# vco1_components.net
KiCad netlist of a schematic drawn in EAGLE
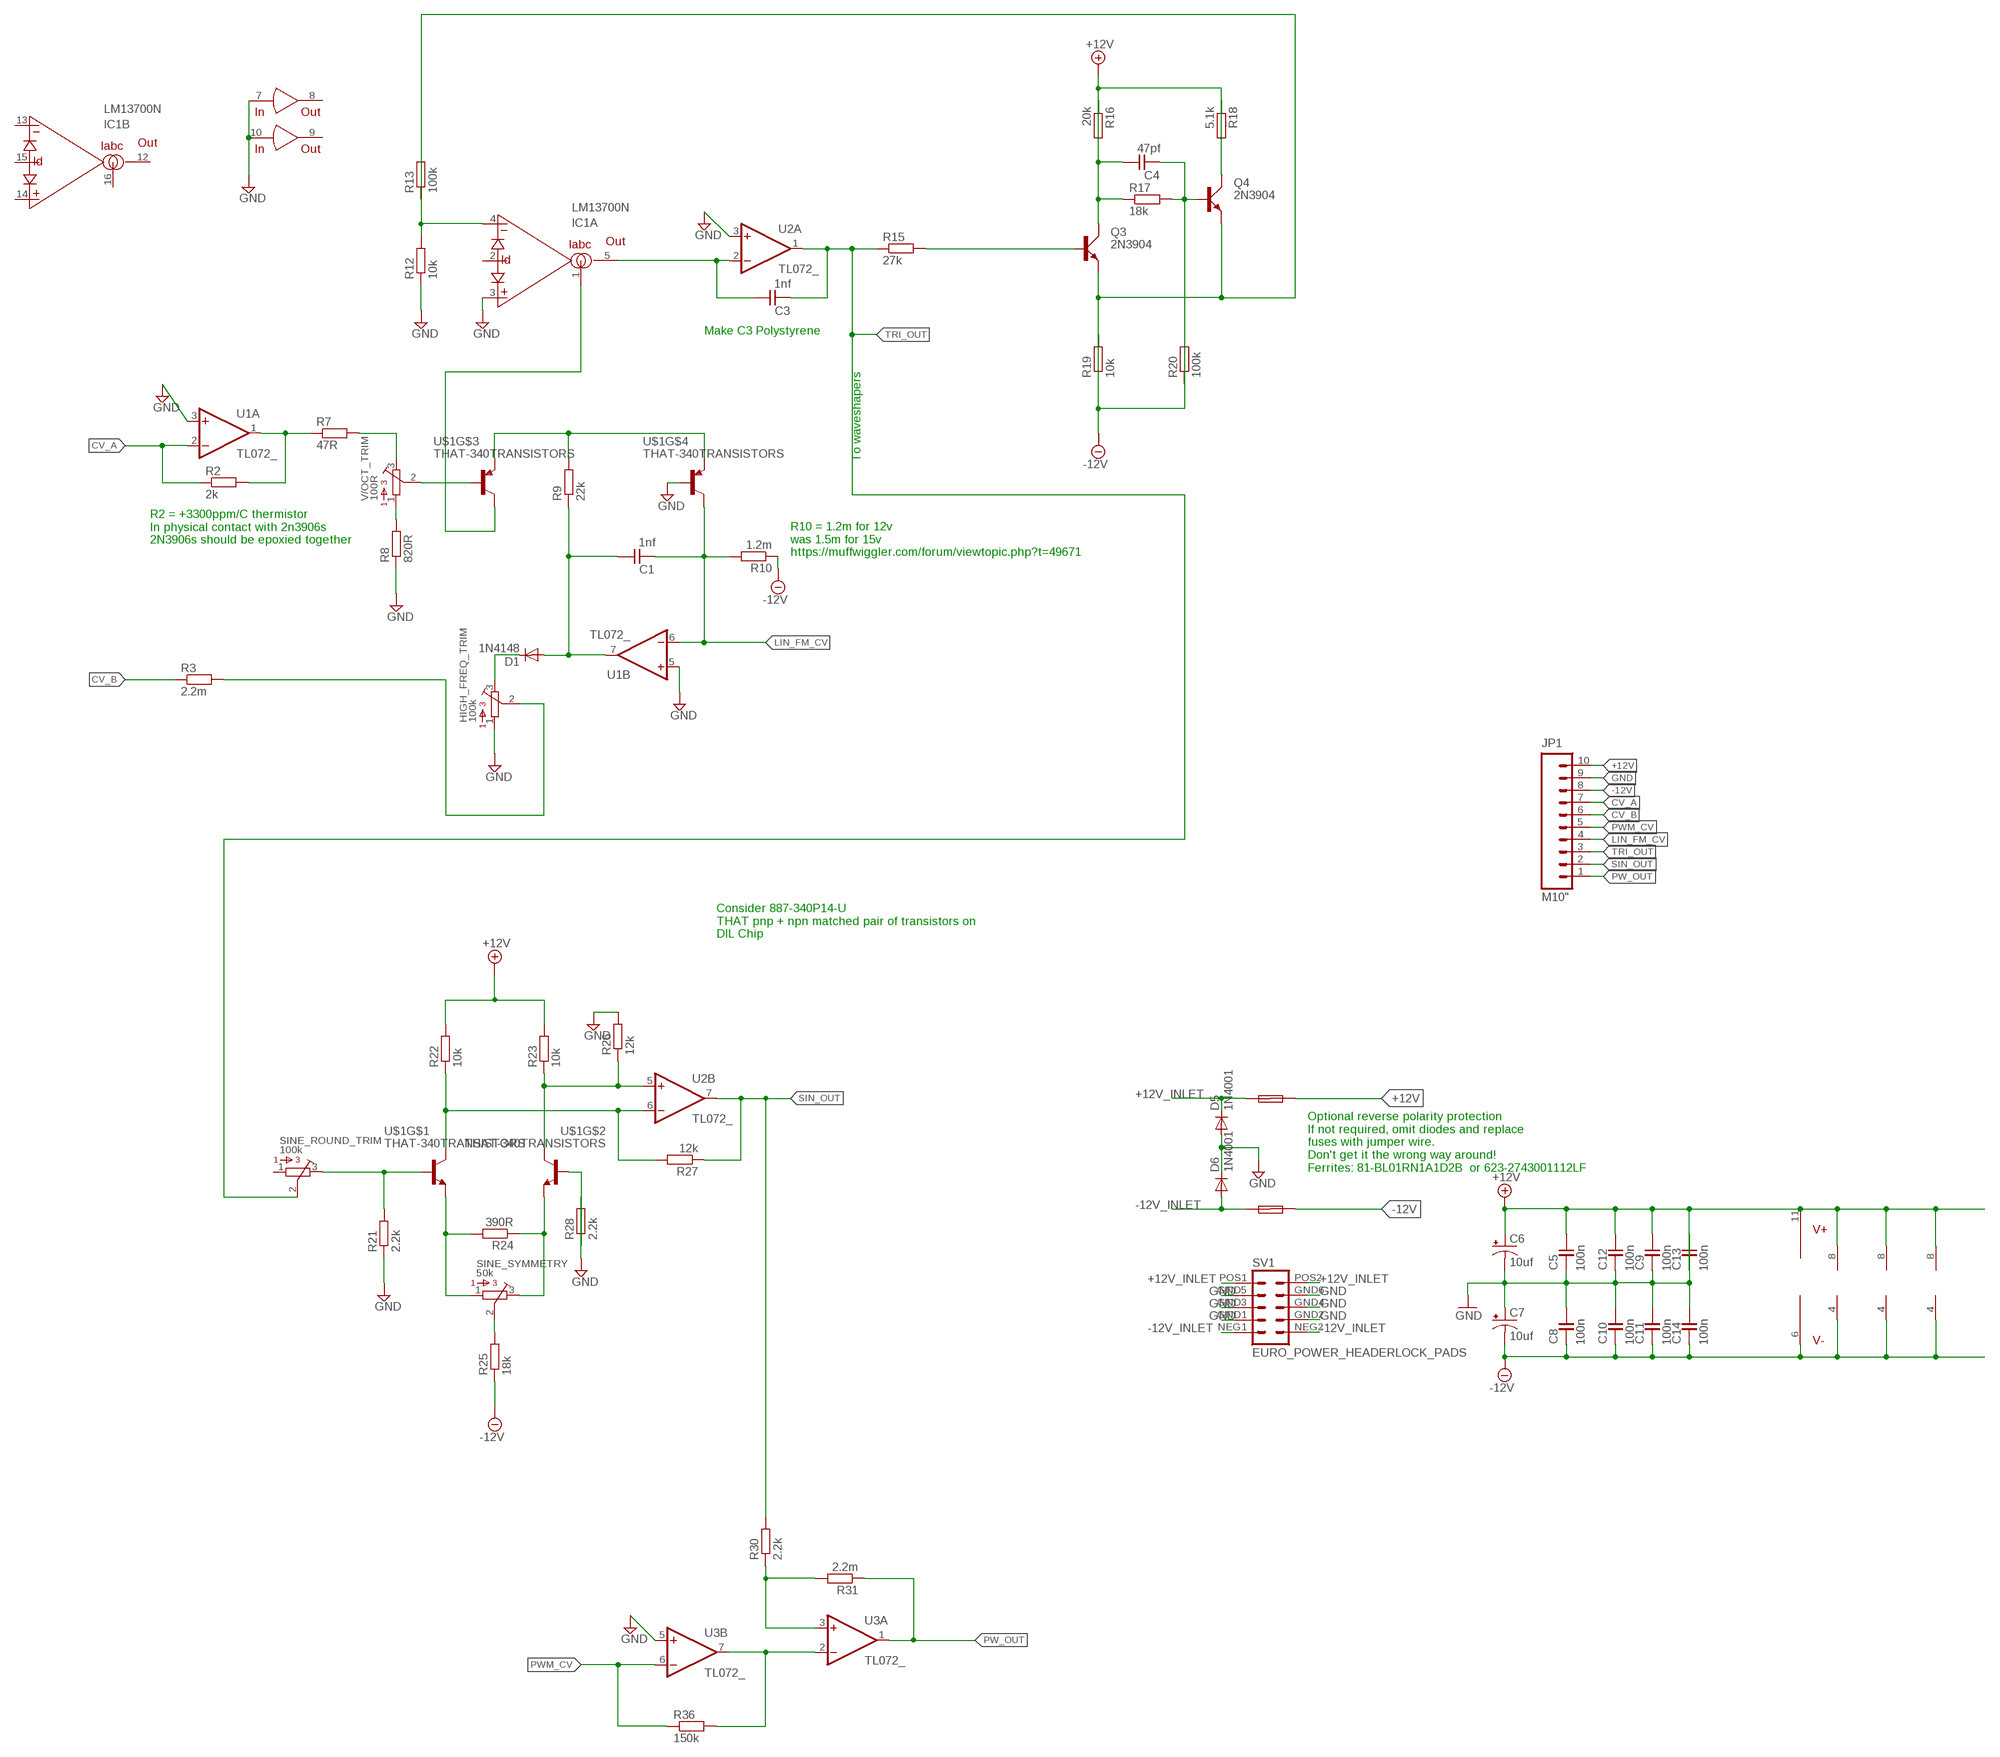
[diagram p0: schematic, sheet 1]

(export (version "E")
  (design (tool "Eeschema 10.0.6"))
  (components
    (comp (ref "C1")
      (value "1nf")
      (footprint "eagle-import:C050-024X044")
      (libsource (lib "eagle-import") (part "C-EU050-024X044"))
    )
    (comp (ref "C3")
      (value "1nf")
      (footprint "eagle-import:C050-024X044")
      (libsource (lib "eagle-import") (part "C-EU050-024X044"))
    )
    (comp (ref "C4")
      (value "47pf")
      (footprint "eagle-import:C050-024X044")
      (libsource (lib "eagle-import") (part "C-EU050-024X044"))
    )
    (comp (ref "C5")
      (value "100n")
      (footprint "eagle-import:C050-024X044")
      (libsource (lib "eagle-import") (part "C-EU050-024X044"))
    )
    (comp (ref "C6")
      (value "10uf")
      (footprint "eagle-import:CPOL-RADIAL-10UF-25V")
      (libsource (lib "eagle-import") (part "CAP_POLPTH2"))
    )
    (comp (ref "C7")
      (value "10uf")
      (footprint "eagle-import:CPOL-RADIAL-10UF-25V")
      (libsource (lib "eagle-import") (part "CAP_POLPTH2"))
    )
    (comp (ref "C8")
      (value "100n")
      (footprint "eagle-import:C050-024X044")
      (libsource (lib "eagle-import") (part "C-EU050-024X044"))
    )
    (comp (ref "C9")
      (value "100n")
      (footprint "eagle-import:C050-024X044")
      (libsource (lib "eagle-import") (part "C-EU050-024X044"))
    )
    (comp (ref "C10")
      (value "100n")
      (footprint "eagle-import:C050-024X044")
      (libsource (lib "eagle-import") (part "C-EU050-024X044"))
    )
    (comp (ref "C11")
      (value "100n")
      (footprint "eagle-import:C050-024X044")
      (libsource (lib "eagle-import") (part "C-EU050-024X044"))
    )
    (comp (ref "C12")
      (value "100n")
      (footprint "eagle-import:C050-024X044")
      (libsource (lib "eagle-import") (part "C-EU050-024X044"))
    )
    (comp (ref "C13")
      (value "100n")
      (footprint "eagle-import:C050-024X044")
      (libsource (lib "eagle-import") (part "C-EU050-024X044"))
    )
    (comp (ref "C14")
      (value "100n")
      (footprint "eagle-import:C050-024X044")
      (libsource (lib "eagle-import") (part "C-EU050-024X044"))
    )
    (comp (ref "D1")
      (value "1N4148")
      (footprint "eagle-import:DO35-7")
      (libsource (lib "eagle-import") (part "SMALL_DIODEDO35-7"))
    )
    (comp (ref "D5")
      (value "1N4001")
      (footprint "eagle-import:DO41-10")
      (libsource (lib "eagle-import") (part "1N4004"))
    )
    (comp (ref "D6")
      (value "1N4001")
      (footprint "eagle-import:DO41-10")
      (libsource (lib "eagle-import") (part "1N4004"))
    )
    (comp (ref "F1")
      (value "FUSE")
      (footprint "eagle-import:C050H075X075")
      (libsource (lib "eagle-import") (part "PTC_FUSEPOLY_FUSE"))
    )
    (comp (ref "F2")
      (value "FUSE")
      (footprint "eagle-import:C050H075X075")
      (libsource (lib "eagle-import") (part "PTC_FUSEPOLY_FUSE"))
    )
    (comp (ref "HIGH_FREQ_TRIM")
      (value "100k")
      (footprint "eagle-import:BOURNS_3362P_TRIMMER")
      (libsource (lib "eagle-import") (part "BOURNS_3362P_TRIMMERP"))
    )
    (comp (ref "IC1")
      (value "LM13700N")
      (footprint "eagle-import:DIL16")
      (libsource (lib "eagle-import") (part "LM13700N"))
    )
    (comp (ref "JP1")
      (value "M10\"")
      (footprint "eagle-import:1X10")
      (libsource (lib "eagle-import") (part "M10{dblquote}"))
    )
    (comp (ref "Q3")
      (value "2N3904")
      (footprint "eagle-import:TO92D")
      (libsource (lib "eagle-import") (part "2N3904"))
    )
    (comp (ref "Q4")
      (value "2N3904")
      (footprint "eagle-import:TO92D")
      (libsource (lib "eagle-import") (part "2N3904"))
    )
    (comp (ref "R2")
      (value "2k")
      (footprint "eagle-import:7MM_RESISTOR")
      (libsource (lib "eagle-import") (part "RESISTOR7MM"))
    )
    (comp (ref "R3")
      (value "2.2m")
      (footprint "eagle-import:7MM_RESISTOR")
      (libsource (lib "eagle-import") (part "RESISTOR7MM"))
    )
    (comp (ref "R7")
      (value "47R")
      (footprint "eagle-import:7MM_RESISTOR")
      (libsource (lib "eagle-import") (part "RESISTOR7MM"))
    )
    (comp (ref "R8")
      (value "820R")
      (footprint "eagle-import:7MM_RESISTOR")
      (libsource (lib "eagle-import") (part "RESISTOR7MM"))
    )
    (comp (ref "R9")
      (value "22k")
      (footprint "eagle-import:7MM_RESISTOR")
      (libsource (lib "eagle-import") (part "RESISTOR7MM"))
    )
    (comp (ref "R10")
      (value "1.2m")
      (footprint "eagle-import:7MM_RESISTOR")
      (libsource (lib "eagle-import") (part "RESISTOR7MM"))
    )
    (comp (ref "R12")
      (value "10k")
      (footprint "eagle-import:7MM_RESISTOR")
      (libsource (lib "eagle-import") (part "RESISTOR7MM"))
    )
    (comp (ref "R13")
      (value "100k")
      (footprint "eagle-import:7MM_RESISTOR")
      (libsource (lib "eagle-import") (part "RESISTOR7MM"))
    )
    (comp (ref "R15")
      (value "27k")
      (footprint "eagle-import:7MM_RESISTOR")
      (libsource (lib "eagle-import") (part "RESISTOR7MM"))
    )
    (comp (ref "R16")
      (value "20k")
      (footprint "eagle-import:7MM_RESISTOR")
      (libsource (lib "eagle-import") (part "RESISTOR7MM"))
    )
    (comp (ref "R17")
      (value "18k")
      (footprint "eagle-import:7MM_RESISTOR")
      (libsource (lib "eagle-import") (part "RESISTOR7MM"))
    )
    (comp (ref "R18")
      (value "5.1k")
      (footprint "eagle-import:7MM_RESISTOR")
      (libsource (lib "eagle-import") (part "RESISTOR7MM"))
    )
    (comp (ref "R19")
      (value "10k")
      (footprint "eagle-import:7MM_RESISTOR")
      (libsource (lib "eagle-import") (part "RESISTOR7MM"))
    )
    (comp (ref "R20")
      (value "100k")
      (footprint "eagle-import:7MM_RESISTOR")
      (libsource (lib "eagle-import") (part "RESISTOR7MM"))
    )
    (comp (ref "R21")
      (value "2.2k")
      (footprint "eagle-import:7MM_RESISTOR")
      (libsource (lib "eagle-import") (part "RESISTOR7MM"))
    )
    (comp (ref "R22")
      (value "10k")
      (footprint "eagle-import:7MM_RESISTOR")
      (libsource (lib "eagle-import") (part "RESISTOR7MM"))
    )
    (comp (ref "R23")
      (value "10k")
      (footprint "eagle-import:7MM_RESISTOR")
      (libsource (lib "eagle-import") (part "RESISTOR7MM"))
    )
    (comp (ref "R24")
      (value "390R")
      (footprint "eagle-import:7MM_RESISTOR")
      (libsource (lib "eagle-import") (part "RESISTOR7MM"))
    )
    (comp (ref "R25")
      (value "18k")
      (footprint "eagle-import:7MM_RESISTOR")
      (libsource (lib "eagle-import") (part "RESISTOR7MM"))
    )
    (comp (ref "R26")
      (value "12k")
      (footprint "eagle-import:7MM_RESISTOR")
      (libsource (lib "eagle-import") (part "RESISTOR7MM"))
    )
    (comp (ref "R27")
      (value "12k")
      (footprint "eagle-import:7MM_RESISTOR")
      (libsource (lib "eagle-import") (part "RESISTOR7MM"))
    )
    (comp (ref "R28")
      (value "2.2k")
      (footprint "eagle-import:7MM_RESISTOR")
      (libsource (lib "eagle-import") (part "RESISTOR7MM"))
    )
    (comp (ref "R30")
      (value "2.2k")
      (footprint "eagle-import:7MM_RESISTOR")
      (libsource (lib "eagle-import") (part "RESISTOR7MM"))
    )
    (comp (ref "R31")
      (value "2.2m")
      (footprint "eagle-import:7MM_RESISTOR")
      (libsource (lib "eagle-import") (part "RESISTOR7MM"))
    )
    (comp (ref "R36")
      (value "150k")
      (footprint "eagle-import:7MM_RESISTOR")
      (libsource (lib "eagle-import") (part "RESISTOR7MM"))
    )
    (comp (ref "SINE_ROUND_TRIM")
      (value "100k")
      (footprint "eagle-import:BOURNS_3362P_TRIMMER")
      (libsource (lib "eagle-import") (part "BOURNS_3362P_TRIMMERP"))
    )
    (comp (ref "SINE_SYMMETRY")
      (value "50k")
      (footprint "eagle-import:BOURNS_3362P_TRIMMER")
      (libsource (lib "eagle-import") (part "BOURNS_3362P_TRIMMERP"))
    )
    (comp (ref "SV1")
      (value "EURO_POWER_HEADERLOCK_PADS")
      (footprint "eagle-import:EURO_PWR_HEADER_LOCK")
      (libsource (lib "eagle-import") (part "EURO_POWER_HEADERLOCK_PADS"))
    )
    (comp (ref "U$1")
      (value "THAT-340TRANSISTORS")
      (footprint "eagle-import:THAT340")
      (libsource (lib "eagle-import") (part "THAT-340TRANSISTORS"))
    )
    (comp (ref "U1")
      (value "TL072_")
      (footprint "eagle-import:DIL08")
      (libsource (lib "eagle-import") (part "TL072_"))
    )
    (comp (ref "U2")
      (value "TL072_")
      (footprint "eagle-import:DIL08")
      (libsource (lib "eagle-import") (part "TL072_"))
    )
    (comp (ref "U3")
      (value "TL072_")
      (footprint "eagle-import:DIL08")
      (libsource (lib "eagle-import") (part "TL072_"))
    )
    (comp (ref "V/OCT_TRIM")
      (value "100R")
      (footprint "eagle-import:BOURNS_3362P_TRIMMER")
      (libsource (lib "eagle-import") (part "BOURNS_3362P_TRIMMERP"))
    )
  )
  (nets
    (net (code "1") (name "+12V") (class "Default")
      (node (ref "C12") (pin "1") (pinfunction "1_1") (pintype "passive"))
      (node (ref "C13") (pin "2") (pinfunction "2_2") (pintype "passive"))
      (node (ref "C5") (pin "1") (pinfunction "1_1") (pintype "passive"))
      (node (ref "C6") (pin "1") (pinfunction "+_1") (pintype "passive"))
      (node (ref "C9") (pin "1") (pinfunction "1_1") (pintype "passive"))
      (node (ref "F1") (pin "2") (pinfunction "P$2_2") (pintype "bidirectional"))
      (node (ref "IC1") (pin "11") (pinfunction "V+_11") (pintype "bidirectional"))
      (node (ref "JP1") (pin "10") (pinfunction "10_10") (pintype "passive"))
      (node (ref "R16") (pin "2") (pinfunction "2_2") (pintype "passive"))
      (node (ref "R18") (pin "2") (pinfunction "2_2") (pintype "passive"))
      (node (ref "R22") (pin "2") (pinfunction "2_2") (pintype "passive"))
      (node (ref "R23") (pin "2") (pinfunction "2_2") (pintype "passive"))
      (node (ref "U1") (pin "8") (pinfunction "V+_8") (pintype "power_in"))
      (node (ref "U2") (pin "8") (pinfunction "V+_8") (pintype "power_in"))
      (node (ref "U3") (pin "8") (pinfunction "V+_8") (pintype "power_in"))
    )
    (net (code "2") (name "-12V") (class "Default")
      (node (ref "C10") (pin "2") (pinfunction "2_2") (pintype "passive"))
      (node (ref "C11") (pin "2") (pinfunction "2_2") (pintype "passive"))
      (node (ref "C14") (pin "2") (pinfunction "2_2") (pintype "passive"))
      (node (ref "C7") (pin "2") (pinfunction "-_2") (pintype "passive"))
      (node (ref "C8") (pin "2") (pinfunction "2_2") (pintype "passive"))
      (node (ref "F2") (pin "2") (pinfunction "P$2_2") (pintype "bidirectional"))
      (node (ref "IC1") (pin "6") (pinfunction "V-_6") (pintype "bidirectional"))
      (node (ref "JP1") (pin "8") (pinfunction "8_8") (pintype "passive"))
      (node (ref "R10") (pin "1") (pinfunction "1_1") (pintype "passive"))
      (node (ref "R19") (pin "2") (pinfunction "2_2") (pintype "passive"))
      (node (ref "R20") (pin "2") (pinfunction "2_2") (pintype "passive"))
      (node (ref "R25") (pin "1") (pinfunction "1_1") (pintype "passive"))
      (node (ref "U1") (pin "4") (pinfunction "V-_4") (pintype "power_in"))
      (node (ref "U2") (pin "4") (pinfunction "V-_4") (pintype "power_in"))
      (node (ref "U3") (pin "4") (pinfunction "V-_4") (pintype "power_in"))
    )
    (net (code "3") (name "/+12V_INLET") (class "Default")
      (node (ref "D5") (pin "C") (pinfunction "C_C") (pintype "passive"))
      (node (ref "F1") (pin "1") (pinfunction "P$1_1") (pintype "bidirectional"))
      (node (ref "SV1") (pin "POS1") (pinfunction "10_POS1") (pintype "passive"))
      (node (ref "SV1") (pin "POS2") (pinfunction "9_POS2") (pintype "passive"))
    )
    (net (code "4") (name "/-12V_INLET") (class "Default")
      (node (ref "D6") (pin "A") (pinfunction "A_A") (pintype "passive"))
      (node (ref "F2") (pin "1") (pinfunction "P$1_1") (pintype "bidirectional"))
      (node (ref "SV1") (pin "NEG1") (pinfunction "2_NEG1") (pintype "passive"))
      (node (ref "SV1") (pin "NEG2") (pinfunction "1_NEG2") (pintype "passive"))
    )
    (net (code "5") (name "CV_A") (class "Default")
      (node (ref "JP1") (pin "7") (pinfunction "7_7") (pintype "passive"))
      (node (ref "R2") (pin "1") (pinfunction "1_1") (pintype "passive"))
      (node (ref "U1") (pin "2") (pinfunction "-IN_2") (pintype "input"))
    )
    (net (code "6") (name "CV_B") (class "Default")
      (node (ref "JP1") (pin "6") (pinfunction "6_6") (pintype "passive"))
      (node (ref "R3") (pin "1") (pinfunction "1_1") (pintype "passive"))
    )
    (net (code "7") (name "GND") (class "Default")
      (node (ref "C10") (pin "1") (pinfunction "1_1") (pintype "passive"))
      (node (ref "C11") (pin "1") (pinfunction "1_1") (pintype "passive"))
      (node (ref "C12") (pin "2") (pinfunction "2_2") (pintype "passive"))
      (node (ref "C13") (pin "1") (pinfunction "1_1") (pintype "passive"))
      (node (ref "C14") (pin "1") (pinfunction "1_1") (pintype "passive"))
      (node (ref "C5") (pin "2") (pinfunction "2_2") (pintype "passive"))
      (node (ref "C6") (pin "2") (pinfunction "-_2") (pintype "passive"))
      (node (ref "C7") (pin "1") (pinfunction "+_1") (pintype "passive"))
      (node (ref "C8") (pin "1") (pinfunction "1_1") (pintype "passive"))
      (node (ref "C9") (pin "2") (pinfunction "2_2") (pintype "passive"))
      (node (ref "D5") (pin "A") (pinfunction "A_A") (pintype "passive"))
      (node (ref "D6") (pin "C") (pinfunction "C_C") (pintype "passive"))
      (node (ref "HIGH_FREQ_TRIM") (pin "1") (pinfunction "1_1") (pintype "passive"))
      (node (ref "IC1") (pin "10") (pinfunction "IN_10") (pintype "bidirectional"))
      (node (ref "IC1") (pin "3") (pinfunction "+IN_3") (pintype "bidirectional"))
      (node (ref "IC1") (pin "7") (pinfunction "IN_7") (pintype "bidirectional"))
      (node (ref "JP1") (pin "9") (pinfunction "9_9") (pintype "passive"))
      (node (ref "R12") (pin "1") (pinfunction "1_1") (pintype "passive"))
      (node (ref "R21") (pin "1") (pinfunction "1_1") (pintype "passive"))
      (node (ref "R26") (pin "2") (pinfunction "2_2") (pintype "passive"))
      (node (ref "R28") (pin "2") (pinfunction "2_2") (pintype "passive"))
      (node (ref "R8") (pin "1") (pinfunction "1_1") (pintype "passive"))
      (node (ref "SV1") (pin "GND1") (pinfunction "4_GND1") (pintype "passive"))
      (node (ref "SV1") (pin "GND2") (pinfunction "3_GND2") (pintype "passive"))
      (node (ref "SV1") (pin "GND3") (pinfunction "6_GND3") (pintype "passive"))
      (node (ref "SV1") (pin "GND4") (pinfunction "5_GND4") (pintype "passive"))
      (node (ref "SV1") (pin "GND5") (pinfunction "8_GND5") (pintype "passive"))
      (node (ref "SV1") (pin "GND6") (pinfunction "7_GND6") (pintype "passive"))
      (node (ref "U$1") (pin "9") (pinfunction "B_9") (pintype "passive"))
      (node (ref "U1") (pin "3") (pinfunction "+IN_3") (pintype "input"))
      (node (ref "U1") (pin "5") (pinfunction "+IN_5") (pintype "input"))
      (node (ref "U2") (pin "3") (pinfunction "+IN_3") (pintype "input"))
      (node (ref "U3") (pin "5") (pinfunction "+IN_5") (pintype "input"))
    )
    (net (code "8") (name "LIN_FM_CV") (class "Default")
      (node (ref "C1") (pin "2") (pinfunction "2_2") (pintype "passive"))
      (node (ref "JP1") (pin "4") (pinfunction "4_4") (pintype "passive"))
      (node (ref "R10") (pin "2") (pinfunction "2_2") (pintype "passive"))
      (node (ref "U$1") (pin "8") (pinfunction "C_8") (pintype "passive"))
      (node (ref "U1") (pin "6") (pinfunction "-IN_6") (pintype "input"))
    )
    (net (code "9") (name "Net-(C4-Pad1)") (class "Default")
      (node (ref "C4") (pin "1") (pinfunction "1_1") (pintype "passive"))
      (node (ref "Q3") (pin "C") (pinfunction "C_C") (pintype "passive"))
      (node (ref "R16") (pin "1") (pinfunction "1_1") (pintype "passive"))
      (node (ref "R17") (pin "1") (pinfunction "1_1") (pintype "passive"))
    )
    (net (code "10") (name "Net-(C4-Pad2)") (class "Default")
      (node (ref "C4") (pin "2") (pinfunction "2_2") (pintype "passive"))
      (node (ref "Q4") (pin "B") (pinfunction "B_B") (pintype "passive"))
      (node (ref "R17") (pin "2") (pinfunction "2_2") (pintype "passive"))
      (node (ref "R20") (pin "1") (pinfunction "1_1") (pintype "passive"))
    )
    (net (code "11") (name "Net-(D1-PadC)") (class "Default")
      (node (ref "D1") (pin "C") (pinfunction "C_C") (pintype "passive"))
      (node (ref "HIGH_FREQ_TRIM") (pin "3") (pinfunction "3_3") (pintype "passive"))
    )
    (net (code "12") (name "Net-(HIGH_FREQ_TRIM-Pad2)") (class "Default")
      (node (ref "HIGH_FREQ_TRIM") (pin "2") (pinfunction "2_2") (pintype "passive"))
      (node (ref "R3") (pin "2") (pinfunction "2_2") (pintype "passive"))
    )
    (net (code "13") (name "Net-(IC1A--IN)") (class "Default")
      (node (ref "IC1") (pin "4") (pinfunction "-IN_4") (pintype "bidirectional"))
      (node (ref "R12") (pin "2") (pinfunction "2_2") (pintype "passive"))
      (node (ref "R13") (pin "2") (pinfunction "2_2") (pintype "passive"))
    )
    (net (code "14") (name "Net-(IC1A-IABC)") (class "Default")
      (node (ref "IC1") (pin "1") (pinfunction "IABC_1") (pintype "bidirectional"))
      (node (ref "U$1") (pin "7") (pinfunction "C_7") (pintype "passive"))
    )
    (net (code "15") (name "Net-(IC1A-OUT)") (class "Default")
      (node (ref "C3") (pin "1") (pinfunction "1_1") (pintype "passive"))
      (node (ref "IC1") (pin "5") (pinfunction "OUT_5") (pintype "bidirectional"))
      (node (ref "U2") (pin "2") (pinfunction "-IN_2") (pintype "input"))
    )
    (net (code "16") (name "Net-(Q3-PadB)") (class "Default")
      (node (ref "Q3") (pin "B") (pinfunction "B_B") (pintype "passive"))
      (node (ref "R15") (pin "2") (pinfunction "2_2") (pintype "passive"))
    )
    (net (code "17") (name "Net-(Q3-PadE)") (class "Default")
      (node (ref "Q3") (pin "E") (pinfunction "E_E") (pintype "passive"))
      (node (ref "Q4") (pin "E") (pinfunction "E_E") (pintype "passive"))
      (node (ref "R13") (pin "1") (pinfunction "1_1") (pintype "passive"))
      (node (ref "R19") (pin "1") (pinfunction "1_1") (pintype "passive"))
    )
    (net (code "18") (name "Net-(Q4-PadC)") (class "Default")
      (node (ref "Q4") (pin "C") (pinfunction "C_C") (pintype "passive"))
      (node (ref "R18") (pin "1") (pinfunction "1_1") (pintype "passive"))
    )
    (net (code "19") (name "Net-(R7-Pad2)") (class "Default")
      (node (ref "R7") (pin "2") (pinfunction "2_2") (pintype "passive"))
      (node (ref "V/OCT_TRIM") (pin "3") (pinfunction "3_3") (pintype "passive"))
    )
    (net (code "20") (name "Net-(R8-Pad2)") (class "Default")
      (node (ref "R8") (pin "2") (pinfunction "2_2") (pintype "passive"))
      (node (ref "V/OCT_TRIM") (pin "1") (pinfunction "1_1") (pintype "passive"))
    )
    (net (code "21") (name "Net-(R25-Pad2)") (class "Default")
      (node (ref "R25") (pin "2") (pinfunction "2_2") (pintype "passive"))
      (node (ref "SINE_SYMMETRY") (pin "2") (pinfunction "2_2") (pintype "passive"))
    )
    (net (code "22") (name "Net-(U$1A-B)") (class "Default")
      (node (ref "R21") (pin "2") (pinfunction "2_2") (pintype "passive"))
      (node (ref "SINE_ROUND_TRIM") (pin "3") (pinfunction "3_3") (pintype "passive"))
      (node (ref "U$1") (pin "2") (pinfunction "B_2") (pintype "passive"))
    )
    (net (code "23") (name "Net-(U$1A-C)") (class "Default")
      (node (ref "R22") (pin "1") (pinfunction "1_1") (pintype "passive"))
      (node (ref "R27") (pin "2") (pinfunction "2_2") (pintype "passive"))
      (node (ref "U$1") (pin "1") (pinfunction "C_1") (pintype "passive"))
      (node (ref "U2") (pin "6") (pinfunction "-IN_6") (pintype "input"))
    )
    (net (code "24") (name "Net-(U$1A-E)") (class "Default")
      (node (ref "R24") (pin "2") (pinfunction "2_2") (pintype "passive"))
      (node (ref "SINE_SYMMETRY") (pin "1") (pinfunction "1_1") (pintype "passive"))
      (node (ref "U$1") (pin "3") (pinfunction "E_3") (pintype "passive"))
    )
    (net (code "25") (name "Net-(U$1B-B)") (class "Default")
      (node (ref "R28") (pin "1") (pinfunction "1_1") (pintype "passive"))
      (node (ref "U$1") (pin "13") (pinfunction "B_13") (pintype "passive"))
    )
    (net (code "26") (name "Net-(U$1B-C)") (class "Default")
      (node (ref "R23") (pin "1") (pinfunction "1_1") (pintype "passive"))
      (node (ref "R26") (pin "1") (pinfunction "1_1") (pintype "passive"))
      (node (ref "U$1") (pin "14") (pinfunction "C_14") (pintype "passive"))
      (node (ref "U2") (pin "5") (pinfunction "+IN_5") (pintype "input"))
    )
    (net (code "27") (name "Net-(U$1B-E)") (class "Default")
      (node (ref "R24") (pin "1") (pinfunction "1_1") (pintype "passive"))
      (node (ref "SINE_SYMMETRY") (pin "3") (pinfunction "3_3") (pintype "passive"))
      (node (ref "U$1") (pin "12") (pinfunction "E_12") (pintype "passive"))
    )
    (net (code "28") (name "Net-(U$1C-B)") (class "Default")
      (node (ref "U$1") (pin "6") (pinfunction "B_6") (pintype "passive"))
      (node (ref "V/OCT_TRIM") (pin "2") (pinfunction "2_2") (pintype "passive"))
    )
    (net (code "29") (name "Net-(U$1C-E)") (class "Default")
      (node (ref "R9") (pin "2") (pinfunction "2_2") (pintype "passive"))
      (node (ref "U$1") (pin "10") (pinfunction "E_10") (pintype "passive"))
      (node (ref "U$1") (pin "5") (pinfunction "E_5") (pintype "passive"))
    )
    (net (code "30") (name "Net-(U1A-OUT)") (class "Default")
      (node (ref "R2") (pin "2") (pinfunction "2_2") (pintype "passive"))
      (node (ref "R7") (pin "1") (pinfunction "1_1") (pintype "passive"))
      (node (ref "U1") (pin "1") (pinfunction "OUT_1") (pintype "output"))
    )
    (net (code "31") (name "Net-(U1B-OUT)") (class "Default")
      (node (ref "C1") (pin "1") (pinfunction "1_1") (pintype "passive"))
      (node (ref "D1") (pin "A") (pinfunction "A_A") (pintype "passive"))
      (node (ref "R9") (pin "1") (pinfunction "1_1") (pintype "passive"))
      (node (ref "U1") (pin "7") (pinfunction "OUT_7") (pintype "output"))
    )
    (net (code "32") (name "Net-(U3A-+IN)") (class "Default")
      (node (ref "R30") (pin "1") (pinfunction "1_1") (pintype "passive"))
      (node (ref "R31") (pin "2") (pinfunction "2_2") (pintype "passive"))
      (node (ref "U3") (pin "3") (pinfunction "+IN_3") (pintype "input"))
    )
    (net (code "33") (name "Net-(U3A--IN)") (class "Default")
      (node (ref "R36") (pin "2") (pinfunction "2_2") (pintype "passive"))
      (node (ref "U3") (pin "2") (pinfunction "-IN_2") (pintype "input"))
      (node (ref "U3") (pin "7") (pinfunction "OUT_7") (pintype "output"))
    )
    (net (code "34") (name "PWM_CV") (class "Default")
      (node (ref "JP1") (pin "5") (pinfunction "5_5") (pintype "passive"))
      (node (ref "R36") (pin "1") (pinfunction "1_1") (pintype "passive"))
      (node (ref "U3") (pin "6") (pinfunction "-IN_6") (pintype "input"))
    )
    (net (code "35") (name "PW_OUT") (class "Default")
      (node (ref "JP1") (pin "1") (pinfunction "1_1") (pintype "passive"))
      (node (ref "R31") (pin "1") (pinfunction "1_1") (pintype "passive"))
      (node (ref "U3") (pin "1") (pinfunction "OUT_1") (pintype "output"))
    )
    (net (code "36") (name "SIN_OUT") (class "Default")
      (node (ref "JP1") (pin "2") (pinfunction "2_2") (pintype "passive"))
      (node (ref "R27") (pin "1") (pinfunction "1_1") (pintype "passive"))
      (node (ref "R30") (pin "2") (pinfunction "2_2") (pintype "passive"))
      (node (ref "U2") (pin "7") (pinfunction "OUT_7") (pintype "output"))
    )
    (net (code "37") (name "TRI_OUT") (class "Default")
      (node (ref "C3") (pin "2") (pinfunction "2_2") (pintype "passive"))
      (node (ref "JP1") (pin "3") (pinfunction "3_3") (pintype "passive"))
      (node (ref "R15") (pin "1") (pinfunction "1_1") (pintype "passive"))
      (node (ref "SINE_ROUND_TRIM") (pin "2") (pinfunction "2_2") (pintype "passive"))
      (node (ref "U2") (pin "1") (pinfunction "OUT_1") (pintype "output"))
    )
    (net (code "38") (name "unconnected-(IC1A-ID-Pad2)") (class "Default")
      (node (ref "IC1") (pin "2") (pinfunction "ID_2") (pintype "bidirectional"))
    )
    (net (code "39") (name "unconnected-(IC1B-+IN-Pad14)") (class "Default")
      (node (ref "IC1") (pin "14") (pinfunction "+IN_14") (pintype "bidirectional"))
    )
    (net (code "40") (name "unconnected-(IC1B--IN-Pad13)") (class "Default")
      (node (ref "IC1") (pin "13") (pinfunction "-IN_13") (pintype "bidirectional"))
    )
    (net (code "41") (name "unconnected-(IC1B-IABC-Pad16)") (class "Default")
      (node (ref "IC1") (pin "16") (pinfunction "IABC_16") (pintype "bidirectional"))
    )
    (net (code "42") (name "unconnected-(IC1B-ID-Pad15)") (class "Default")
      (node (ref "IC1") (pin "15") (pinfunction "ID_15") (pintype "bidirectional"))
    )
    (net (code "43") (name "unconnected-(IC1B-OUT-Pad12)") (class "Default")
      (node (ref "IC1") (pin "12") (pinfunction "OUT_12") (pintype "bidirectional"))
    )
    (net (code "44") (name "unconnected-(IC1C-OUT-Pad8)") (class "Default")
      (node (ref "IC1") (pin "8") (pinfunction "OUT_8") (pintype "bidirectional"))
    )
    (net (code "45") (name "unconnected-(IC1D-OUT-Pad9)") (class "Default")
      (node (ref "IC1") (pin "9") (pinfunction "OUT_9") (pintype "bidirectional"))
    )
    (net (code "46") (name "unconnected-(SINE_ROUND_TRIM-Pad1)") (class "Default")
      (node (ref "SINE_ROUND_TRIM") (pin "1") (pinfunction "1_1") (pintype "passive"))
    )
  )
)
